# Sensor_board.net
KiCad netlist of a schematic drawn in EAGLE
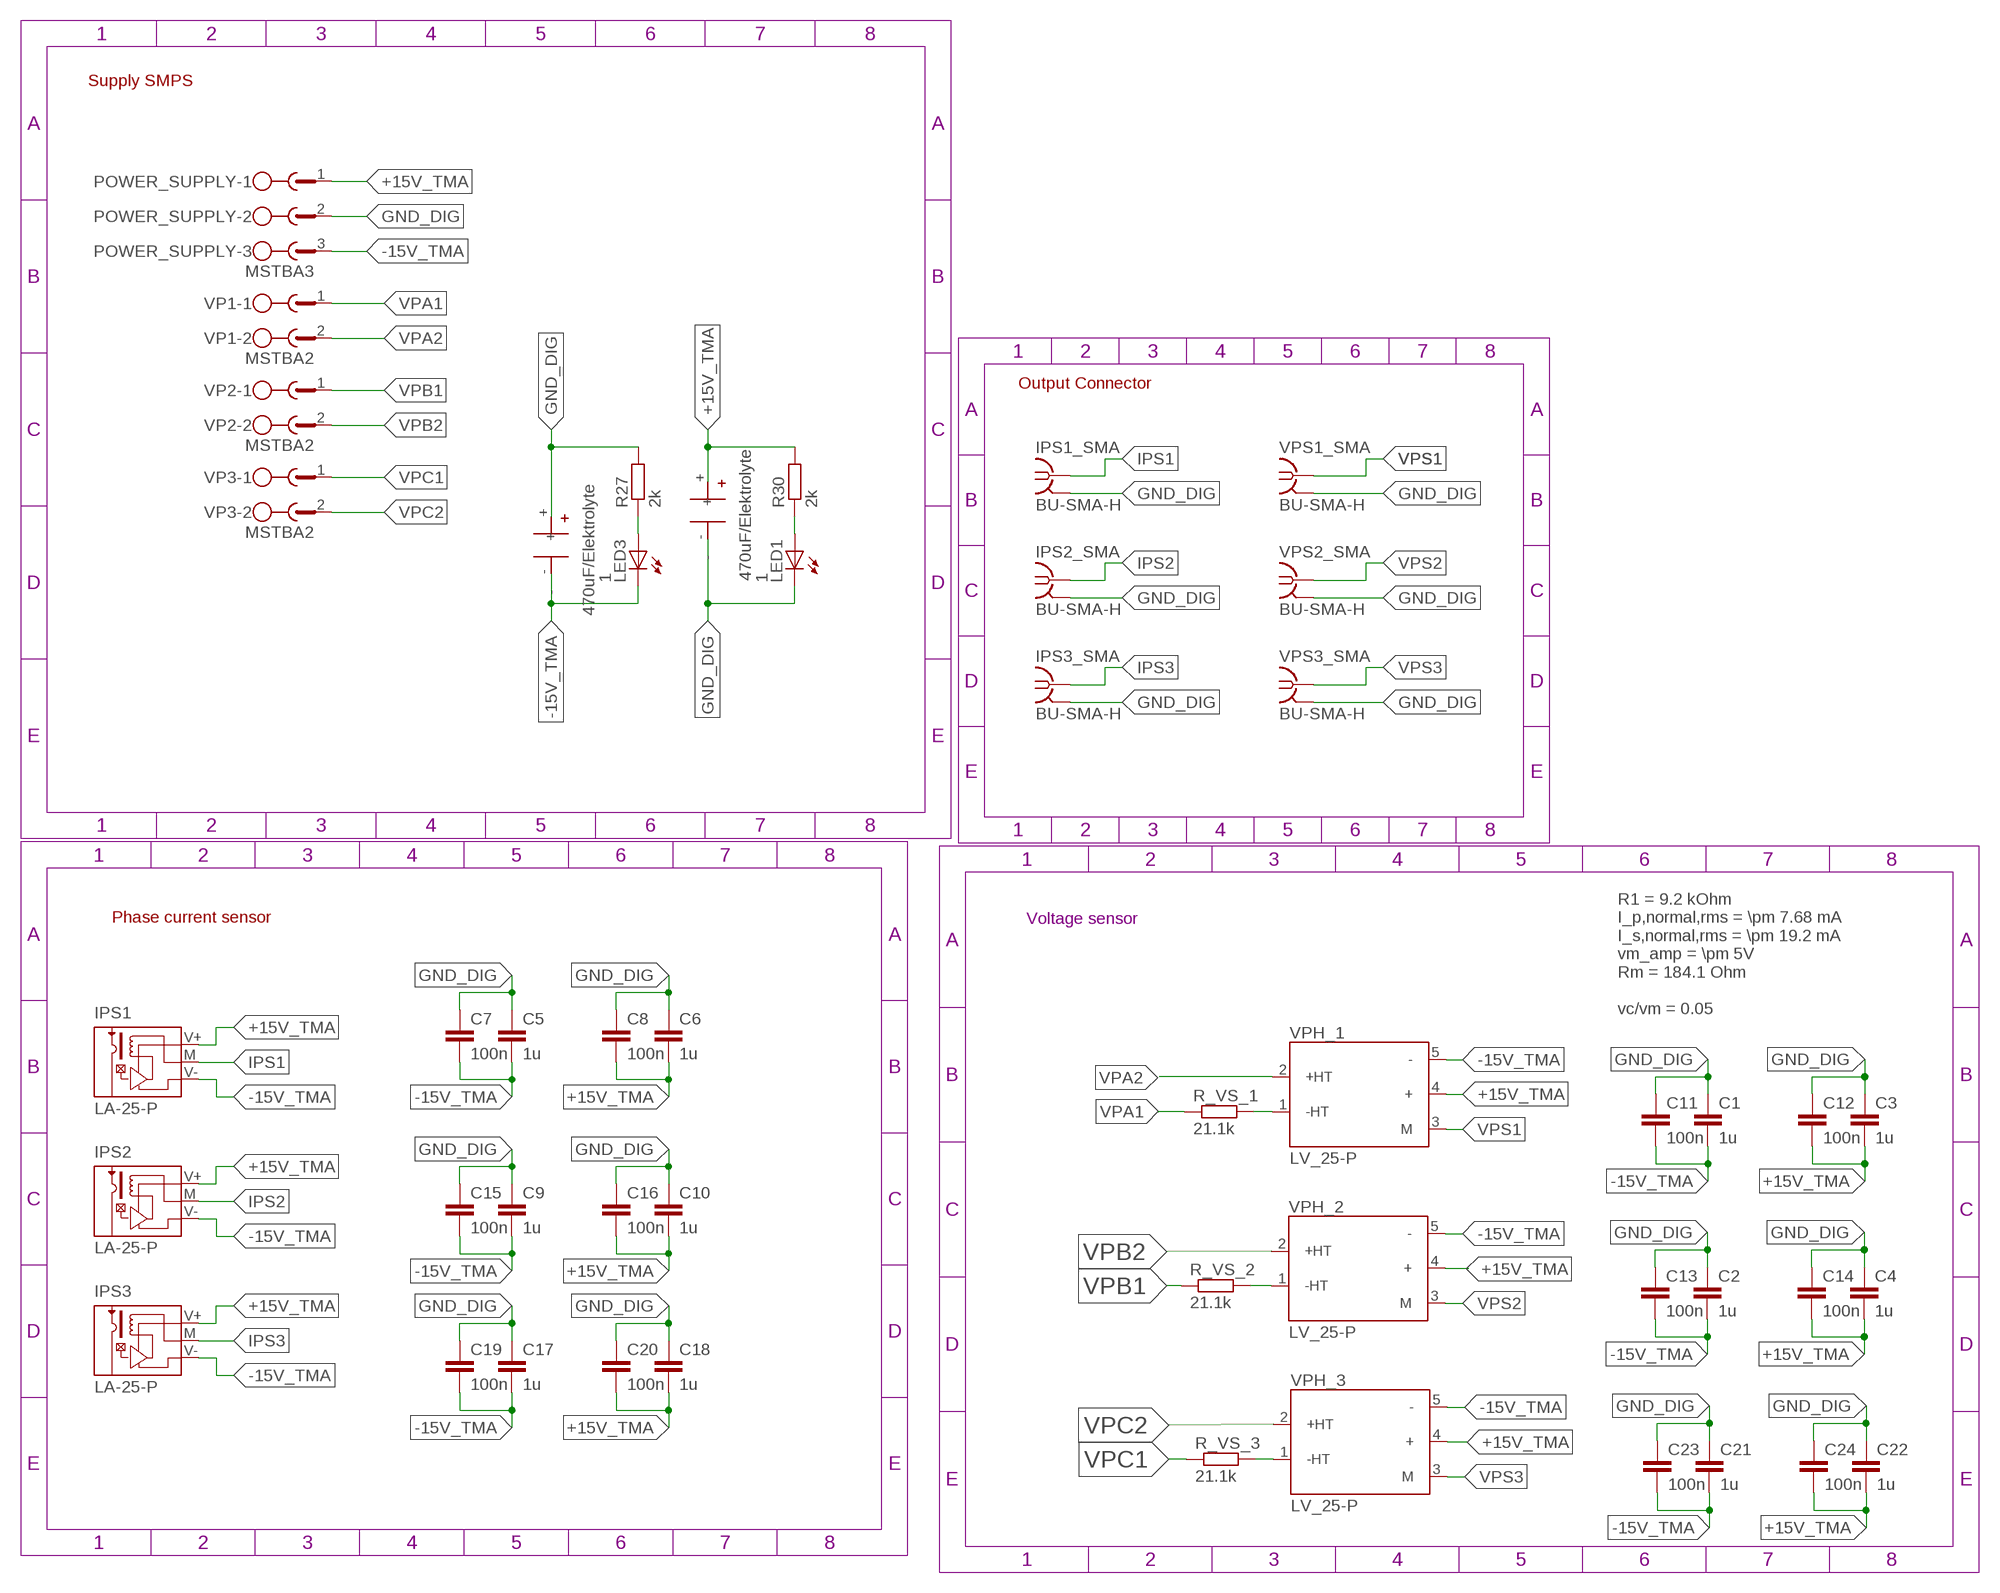
[diagram p0: schematic, sheet 1]

(export (version "E")
  (design (tool "Eeschema 10.0.6"))
  (components
    (comp (ref "C1")
      (value "1u")
      (footprint "eagle-import:C0805")
      (libsource (lib "eagle-import") (part "C-EUC0805"))
    )
    (comp (ref "C2")
      (value "1u")
      (footprint "eagle-import:C0805")
      (libsource (lib "eagle-import") (part "C-EUC0805"))
    )
    (comp (ref "C3")
      (value "1u")
      (footprint "eagle-import:C0805")
      (libsource (lib "eagle-import") (part "C-EUC0805"))
    )
    (comp (ref "C4")
      (value "1u")
      (footprint "eagle-import:C0805")
      (libsource (lib "eagle-import") (part "C-EUC0805"))
    )
    (comp (ref "C5")
      (value "1u")
      (footprint "eagle-import:C0805")
      (libsource (lib "eagle-import") (part "C-EUC0805"))
    )
    (comp (ref "C6")
      (value "1u")
      (footprint "eagle-import:C0805")
      (libsource (lib "eagle-import") (part "C-EUC0805"))
    )
    (comp (ref "C7")
      (value "100n")
      (footprint "eagle-import:C0805")
      (libsource (lib "eagle-import") (part "C-EUC0805"))
    )
    (comp (ref "C8")
      (value "100n")
      (footprint "eagle-import:C0805")
      (libsource (lib "eagle-import") (part "C-EUC0805"))
    )
    (comp (ref "C9")
      (value "1u")
      (footprint "eagle-import:C0805")
      (libsource (lib "eagle-import") (part "C-EUC0805"))
    )
    (comp (ref "C10")
      (value "1u")
      (footprint "eagle-import:C0805")
      (libsource (lib "eagle-import") (part "C-EUC0805"))
    )
    (comp (ref "C11")
      (value "100n")
      (footprint "eagle-import:C0805")
      (libsource (lib "eagle-import") (part "C-EUC0805"))
    )
    (comp (ref "C12")
      (value "100n")
      (footprint "eagle-import:C0805")
      (libsource (lib "eagle-import") (part "C-EUC0805"))
    )
    (comp (ref "C13")
      (value "100n")
      (footprint "eagle-import:C0805")
      (libsource (lib "eagle-import") (part "C-EUC0805"))
    )
    (comp (ref "C14")
      (value "100n")
      (footprint "eagle-import:C0805")
      (libsource (lib "eagle-import") (part "C-EUC0805"))
    )
    (comp (ref "C15")
      (value "100n")
      (footprint "eagle-import:C0805")
      (libsource (lib "eagle-import") (part "C-EUC0805"))
    )
    (comp (ref "C16")
      (value "100n")
      (footprint "eagle-import:C0805")
      (libsource (lib "eagle-import") (part "C-EUC0805"))
    )
    (comp (ref "C17")
      (value "1u")
      (footprint "eagle-import:C0805")
      (libsource (lib "eagle-import") (part "C-EUC0805"))
    )
    (comp (ref "C18")
      (value "1u")
      (footprint "eagle-import:C0805")
      (libsource (lib "eagle-import") (part "C-EUC0805"))
    )
    (comp (ref "C19")
      (value "100n")
      (footprint "eagle-import:C0805")
      (libsource (lib "eagle-import") (part "C-EUC0805"))
    )
    (comp (ref "C20")
      (value "100n")
      (footprint "eagle-import:C0805")
      (libsource (lib "eagle-import") (part "C-EUC0805"))
    )
    (comp (ref "C21")
      (value "1u")
      (footprint "eagle-import:C0805")
      (libsource (lib "eagle-import") (part "C-EUC0805"))
    )
    (comp (ref "C22")
      (value "1u")
      (footprint "eagle-import:C0805")
      (libsource (lib "eagle-import") (part "C-EUC0805"))
    )
    (comp (ref "C23")
      (value "100n")
      (footprint "eagle-import:C0805")
      (libsource (lib "eagle-import") (part "C-EUC0805"))
    )
    (comp (ref "C24")
      (value "100n")
      (footprint "eagle-import:C0805")
      (libsource (lib "eagle-import") (part "C-EUC0805"))
    )
    (comp (ref "C31")
      (value "ELE_C_470UF_PAN")
      (footprint "eagle-import:ELEK_C_470UF_PAN")
      (libsource (lib "eagle-import") (part "ELE_C_470UF_PAN"))
    )
    (comp (ref "C32")
      (value "ELE_C_470UF_PAN")
      (footprint "eagle-import:ELEK_C_470UF_PAN")
      (libsource (lib "eagle-import") (part "ELE_C_470UF_PAN"))
    )
    (comp (ref "IPS1")
      (value "LA-25-P")
      (footprint "eagle-import:LA25P")
      (libsource (lib "eagle-import") (part "LA-25-P"))
    )
    (comp (ref "IPS1_SMA")
      (value "BU-SMA-H")
      (footprint "eagle-import:BU-SMA-H")
      (libsource (lib "eagle-import") (part "BU-SMA-H"))
    )
    (comp (ref "IPS2")
      (value "LA-25-P")
      (footprint "eagle-import:LA25P")
      (libsource (lib "eagle-import") (part "LA-25-P"))
    )
    (comp (ref "IPS2_SMA")
      (value "BU-SMA-H")
      (footprint "eagle-import:BU-SMA-H")
      (libsource (lib "eagle-import") (part "BU-SMA-H"))
    )
    (comp (ref "IPS3")
      (value "LA-25-P")
      (footprint "eagle-import:LA25P")
      (libsource (lib "eagle-import") (part "LA-25-P"))
    )
    (comp (ref "IPS3_SMA")
      (value "BU-SMA-H")
      (footprint "eagle-import:BU-SMA-H")
      (libsource (lib "eagle-import") (part "BU-SMA-H"))
    )
    (comp (ref "LED1")
      (value "1")
      (footprint "eagle-import:CHIPLED_0805")
      (libsource (lib "eagle-import") (part "LEDCHIPLED_0805"))
    )
    (comp (ref "LED3")
      (value "1")
      (footprint "eagle-import:CHIPLED_0805")
      (libsource (lib "eagle-import") (part "LEDCHIPLED_0805"))
    )
    (comp (ref "POWER_SUPPLY")
      (value "MSTBA3")
      (footprint "eagle-import:MSTBA3")
      (fields (field (name "MF") "FARNELL") (field (name "MPN") "1757255"))
      (libsource (lib "eagle-import") (part "MSTBA3"))
    )
    (comp (ref "R27")
      (value "2k")
      (footprint "eagle-import:R0805")
      (libsource (lib "eagle-import") (part "R-EU_R0805"))
    )
    (comp (ref "R30")
      (value "2k")
      (footprint "eagle-import:R0805")
      (libsource (lib "eagle-import") (part "R-EU_R0805"))
    )
    (comp (ref "R_VS_1")
      (value "21.1k")
      (footprint "eagle-import:0414_15")
      (libsource (lib "eagle-import") (part "R-EU_0414/15"))
    )
    (comp (ref "R_VS_2")
      (value "21.1k")
      (footprint "eagle-import:0414_15")
      (libsource (lib "eagle-import") (part "R-EU_0414/15"))
    )
    (comp (ref "R_VS_3")
      (value "21.1k")
      (footprint "eagle-import:0414_15")
      (libsource (lib "eagle-import") (part "R-EU_0414/15"))
    )
    (comp (ref "VP1")
      (value "MSTBA2")
      (footprint "eagle-import:MSTBA2")
      (fields (field (name "MF") "FARNELL") (field (name "MPN") "1757242"))
      (libsource (lib "eagle-import") (part "MSTBA2"))
    )
    (comp (ref "VP2")
      (value "MSTBA2")
      (footprint "eagle-import:MSTBA2")
      (fields (field (name "MF") "FARNELL") (field (name "MPN") "1757242"))
      (libsource (lib "eagle-import") (part "MSTBA2"))
    )
    (comp (ref "VP3")
      (value "MSTBA2")
      (footprint "eagle-import:MSTBA2")
      (fields (field (name "MF") "FARNELL") (field (name "MPN") "1757242"))
      (libsource (lib "eagle-import") (part "MSTBA2"))
    )
    (comp (ref "VPH_1")
      (value "LV_25-P")
      (footprint "eagle-import:XDCR_LV25-P")
      (fields
        (field (name "DIGI-KEY_PART_NUMBER") "398-1019-ND")
        (field (name "MF") "LEM USA")
        (field (name "MP") "LV 25-P")
      )
      (libsource (lib "eagle-import") (part "LV_25-P"))
    )
    (comp (ref "VPH_2")
      (value "LV_25-P")
      (footprint "eagle-import:XDCR_LV25-P")
      (fields
        (field (name "DIGI-KEY_PART_NUMBER") "398-1019-ND")
        (field (name "MF") "LEM USA")
        (field (name "MP") "LV 25-P")
      )
      (libsource (lib "eagle-import") (part "LV_25-P"))
    )
    (comp (ref "VPH_3")
      (value "LV_25-P")
      (footprint "eagle-import:XDCR_LV25-P")
      (fields
        (field (name "DIGI-KEY_PART_NUMBER") "398-1019-ND")
        (field (name "MF") "LEM USA")
        (field (name "MP") "LV 25-P")
      )
      (libsource (lib "eagle-import") (part "LV_25-P"))
    )
    (comp (ref "VPS1_SMA")
      (value "BU-SMA-H")
      (footprint "eagle-import:BU-SMA-H")
      (libsource (lib "eagle-import") (part "BU-SMA-H"))
    )
    (comp (ref "VPS2_SMA")
      (value "BU-SMA-H")
      (footprint "eagle-import:BU-SMA-H")
      (libsource (lib "eagle-import") (part "BU-SMA-H"))
    )
    (comp (ref "VPS3_SMA")
      (value "BU-SMA-H")
      (footprint "eagle-import:BU-SMA-H")
      (libsource (lib "eagle-import") (part "BU-SMA-H"))
    )
  )
  (nets
    (net (code "1") (name "+15V_TMA") (class "Default")
      (node (ref "C10") (pin "2") (pinfunction "2_2") (pintype "passive"))
      (node (ref "C12") (pin "2") (pinfunction "2_2") (pintype "passive"))
      (node (ref "C14") (pin "2") (pinfunction "2_2") (pintype "passive"))
      (node (ref "C16") (pin "2") (pinfunction "2_2") (pintype "passive"))
      (node (ref "C18") (pin "2") (pinfunction "2_2") (pintype "passive"))
      (node (ref "C20") (pin "2") (pinfunction "2_2") (pintype "passive"))
      (node (ref "C22") (pin "2") (pinfunction "2_2") (pintype "passive"))
      (node (ref "C24") (pin "2") (pinfunction "2_2") (pintype "passive"))
      (node (ref "C3") (pin "2") (pinfunction "2_2") (pintype "passive"))
      (node (ref "C32") (pin "+") (pinfunction "+_+") (pintype "bidirectional"))
      (node (ref "C4") (pin "2") (pinfunction "2_2") (pintype "passive"))
      (node (ref "C6") (pin "2") (pinfunction "2_2") (pintype "passive"))
      (node (ref "C8") (pin "2") (pinfunction "2_2") (pintype "passive"))
      (node (ref "IPS1") (pin "V+") (pinfunction "V+_V+") (pintype "input"))
      (node (ref "IPS2") (pin "V+") (pinfunction "V+_V+") (pintype "input"))
      (node (ref "IPS3") (pin "V+") (pinfunction "V+_V+") (pintype "input"))
      (node (ref "POWER_SUPPLY") (pin "1") (pinfunction "1_1") (pintype "passive"))
      (node (ref "R30") (pin "2") (pinfunction "2_2") (pintype "passive"))
      (node (ref "VPH_1") (pin "4") (pinfunction "+_4") (pintype "output"))
      (node (ref "VPH_2") (pin "4") (pinfunction "+_4") (pintype "output"))
      (node (ref "VPH_3") (pin "4") (pinfunction "+_4") (pintype "output"))
    )
    (net (code "2") (name "-15V_TMA") (class "Default")
      (node (ref "C1") (pin "2") (pinfunction "2_2") (pintype "passive"))
      (node (ref "C11") (pin "2") (pinfunction "2_2") (pintype "passive"))
      (node (ref "C13") (pin "2") (pinfunction "2_2") (pintype "passive"))
      (node (ref "C15") (pin "2") (pinfunction "2_2") (pintype "passive"))
      (node (ref "C17") (pin "2") (pinfunction "2_2") (pintype "passive"))
      (node (ref "C19") (pin "2") (pinfunction "2_2") (pintype "passive"))
      (node (ref "C2") (pin "2") (pinfunction "2_2") (pintype "passive"))
      (node (ref "C21") (pin "2") (pinfunction "2_2") (pintype "passive"))
      (node (ref "C23") (pin "2") (pinfunction "2_2") (pintype "passive"))
      (node (ref "C31") (pin "-") (pinfunction "-_-") (pintype "bidirectional"))
      (node (ref "C5") (pin "2") (pinfunction "2_2") (pintype "passive"))
      (node (ref "C7") (pin "2") (pinfunction "2_2") (pintype "passive"))
      (node (ref "C9") (pin "2") (pinfunction "2_2") (pintype "passive"))
      (node (ref "IPS1") (pin "V-") (pinfunction "V-_V-") (pintype "input"))
      (node (ref "IPS2") (pin "V-") (pinfunction "V-_V-") (pintype "input"))
      (node (ref "IPS3") (pin "V-") (pinfunction "V-_V-") (pintype "input"))
      (node (ref "LED3") (pin "C") (pinfunction "C_C") (pintype "passive"))
      (node (ref "POWER_SUPPLY") (pin "3") (pinfunction "1_3") (pintype "passive"))
      (node (ref "VPH_1") (pin "5") (pinfunction "-_5") (pintype "output"))
      (node (ref "VPH_2") (pin "5") (pinfunction "-_5") (pintype "output"))
      (node (ref "VPH_3") (pin "5") (pinfunction "-_5") (pintype "output"))
    )
    (net (code "3") (name "GND_DIG") (class "Default")
      (node (ref "C1") (pin "1") (pinfunction "1_1") (pintype "passive"))
      (node (ref "C10") (pin "1") (pinfunction "1_1") (pintype "passive"))
      (node (ref "C11") (pin "1") (pinfunction "1_1") (pintype "passive"))
      (node (ref "C12") (pin "1") (pinfunction "1_1") (pintype "passive"))
      (node (ref "C13") (pin "1") (pinfunction "1_1") (pintype "passive"))
      (node (ref "C14") (pin "1") (pinfunction "1_1") (pintype "passive"))
      (node (ref "C15") (pin "1") (pinfunction "1_1") (pintype "passive"))
      (node (ref "C16") (pin "1") (pinfunction "1_1") (pintype "passive"))
      (node (ref "C17") (pin "1") (pinfunction "1_1") (pintype "passive"))
      (node (ref "C18") (pin "1") (pinfunction "1_1") (pintype "passive"))
      (node (ref "C19") (pin "1") (pinfunction "1_1") (pintype "passive"))
      (node (ref "C2") (pin "1") (pinfunction "1_1") (pintype "passive"))
      (node (ref "C20") (pin "1") (pinfunction "1_1") (pintype "passive"))
      (node (ref "C21") (pin "1") (pinfunction "1_1") (pintype "passive"))
      (node (ref "C22") (pin "1") (pinfunction "1_1") (pintype "passive"))
      (node (ref "C23") (pin "1") (pinfunction "1_1") (pintype "passive"))
      (node (ref "C24") (pin "1") (pinfunction "1_1") (pintype "passive"))
      (node (ref "C3") (pin "1") (pinfunction "1_1") (pintype "passive"))
      (node (ref "C31") (pin "+") (pinfunction "+_+") (pintype "bidirectional"))
      (node (ref "C32") (pin "-") (pinfunction "-_-") (pintype "bidirectional"))
      (node (ref "C4") (pin "1") (pinfunction "1_1") (pintype "passive"))
      (node (ref "C5") (pin "1") (pinfunction "1_1") (pintype "passive"))
      (node (ref "C6") (pin "1") (pinfunction "1_1") (pintype "passive"))
      (node (ref "C7") (pin "1") (pinfunction "1_1") (pintype "passive"))
      (node (ref "C8") (pin "1") (pinfunction "1_1") (pintype "passive"))
      (node (ref "C9") (pin "1") (pinfunction "1_1") (pintype "passive"))
      (node (ref "IPS1_SMA") (pin "2") (pinfunction "2_2") (pintype "passive"))
      (node (ref "IPS1_SMA") (pin "3") (pinfunction "2_3") (pintype "passive"))
      (node (ref "IPS1_SMA") (pin "4") (pinfunction "2_4") (pintype "passive"))
      (node (ref "IPS1_SMA") (pin "5") (pinfunction "2_5") (pintype "passive"))
      (node (ref "IPS2_SMA") (pin "2") (pinfunction "2_2") (pintype "passive"))
      (node (ref "IPS2_SMA") (pin "3") (pinfunction "2_3") (pintype "passive"))
      (node (ref "IPS2_SMA") (pin "4") (pinfunction "2_4") (pintype "passive"))
      (node (ref "IPS2_SMA") (pin "5") (pinfunction "2_5") (pintype "passive"))
      (node (ref "IPS3_SMA") (pin "2") (pinfunction "2_2") (pintype "passive"))
      (node (ref "IPS3_SMA") (pin "3") (pinfunction "2_3") (pintype "passive"))
      (node (ref "IPS3_SMA") (pin "4") (pinfunction "2_4") (pintype "passive"))
      (node (ref "IPS3_SMA") (pin "5") (pinfunction "2_5") (pintype "passive"))
      (node (ref "LED1") (pin "C") (pinfunction "C_C") (pintype "passive"))
      (node (ref "POWER_SUPPLY") (pin "2") (pinfunction "1_2") (pintype "passive"))
      (node (ref "R27") (pin "2") (pinfunction "2_2") (pintype "passive"))
      (node (ref "VPS1_SMA") (pin "2") (pinfunction "2_2") (pintype "passive"))
      (node (ref "VPS1_SMA") (pin "3") (pinfunction "2_3") (pintype "passive"))
      (node (ref "VPS1_SMA") (pin "4") (pinfunction "2_4") (pintype "passive"))
      (node (ref "VPS1_SMA") (pin "5") (pinfunction "2_5") (pintype "passive"))
      (node (ref "VPS2_SMA") (pin "2") (pinfunction "2_2") (pintype "passive"))
      (node (ref "VPS2_SMA") (pin "3") (pinfunction "2_3") (pintype "passive"))
      (node (ref "VPS2_SMA") (pin "4") (pinfunction "2_4") (pintype "passive"))
      (node (ref "VPS2_SMA") (pin "5") (pinfunction "2_5") (pintype "passive"))
      (node (ref "VPS3_SMA") (pin "2") (pinfunction "2_2") (pintype "passive"))
      (node (ref "VPS3_SMA") (pin "3") (pinfunction "2_3") (pintype "passive"))
      (node (ref "VPS3_SMA") (pin "4") (pinfunction "2_4") (pintype "passive"))
      (node (ref "VPS3_SMA") (pin "5") (pinfunction "2_5") (pintype "passive"))
    )
    (net (code "4") (name "IPS1") (class "Default")
      (node (ref "IPS1") (pin "M") (pinfunction "M_M") (pintype "output"))
      (node (ref "IPS1_SMA") (pin "1") (pinfunction "1_1") (pintype "passive"))
    )
    (net (code "5") (name "IPS2") (class "Default")
      (node (ref "IPS2") (pin "M") (pinfunction "M_M") (pintype "output"))
      (node (ref "IPS2_SMA") (pin "1") (pinfunction "1_1") (pintype "passive"))
    )
    (net (code "6") (name "IPS3") (class "Default")
      (node (ref "IPS3") (pin "M") (pinfunction "M_M") (pintype "output"))
      (node (ref "IPS3_SMA") (pin "1") (pinfunction "1_1") (pintype "passive"))
    )
    (net (code "7") (name "Net-(LED1-PadA)") (class "Default")
      (node (ref "LED1") (pin "A") (pinfunction "A_A") (pintype "passive"))
      (node (ref "R30") (pin "1") (pinfunction "1_1") (pintype "passive"))
    )
    (net (code "8") (name "Net-(LED3-PadA)") (class "Default")
      (node (ref "LED3") (pin "A") (pinfunction "A_A") (pintype "passive"))
      (node (ref "R27") (pin "1") (pinfunction "1_1") (pintype "passive"))
    )
    (net (code "9") (name "Net-(VPH_1--HT)") (class "Default")
      (node (ref "R_VS_1") (pin "2") (pinfunction "2_2") (pintype "passive"))
      (node (ref "VPH_1") (pin "1") (pinfunction "-HT_1") (pintype "input"))
    )
    (net (code "10") (name "Net-(VPH_2--HT)") (class "Default")
      (node (ref "R_VS_2") (pin "2") (pinfunction "2_2") (pintype "passive"))
      (node (ref "VPH_2") (pin "1") (pinfunction "-HT_1") (pintype "input"))
    )
    (net (code "11") (name "Net-(VPH_3--HT)") (class "Default")
      (node (ref "R_VS_3") (pin "2") (pinfunction "2_2") (pintype "passive"))
      (node (ref "VPH_3") (pin "1") (pinfunction "-HT_1") (pintype "input"))
    )
    (net (code "12") (name "VPA1") (class "Default")
      (node (ref "R_VS_1") (pin "1") (pinfunction "1_1") (pintype "passive"))
      (node (ref "VP1") (pin "1") (pinfunction "1_1") (pintype "passive"))
    )
    (net (code "13") (name "VPA2") (class "Default")
      (node (ref "VP1") (pin "2") (pinfunction "1_2") (pintype "passive"))
      (node (ref "VPH_1") (pin "2") (pinfunction "+HT_2") (pintype "input"))
    )
    (net (code "14") (name "VPB1") (class "Default")
      (node (ref "R_VS_2") (pin "1") (pinfunction "1_1") (pintype "passive"))
      (node (ref "VP2") (pin "1") (pinfunction "1_1") (pintype "passive"))
    )
    (net (code "15") (name "VPB2") (class "Default")
      (node (ref "VP2") (pin "2") (pinfunction "1_2") (pintype "passive"))
      (node (ref "VPH_2") (pin "2") (pinfunction "+HT_2") (pintype "input"))
    )
    (net (code "16") (name "VPC1") (class "Default")
      (node (ref "R_VS_3") (pin "1") (pinfunction "1_1") (pintype "passive"))
      (node (ref "VP3") (pin "1") (pinfunction "1_1") (pintype "passive"))
    )
    (net (code "17") (name "VPC2") (class "Default")
      (node (ref "VP3") (pin "2") (pinfunction "1_2") (pintype "passive"))
      (node (ref "VPH_3") (pin "2") (pinfunction "+HT_2") (pintype "input"))
    )
    (net (code "18") (name "VPS1") (class "Default")
      (node (ref "VPH_1") (pin "3") (pinfunction "M_3") (pintype "output"))
      (node (ref "VPS1_SMA") (pin "1") (pinfunction "1_1") (pintype "passive"))
    )
    (net (code "19") (name "VPS2") (class "Default")
      (node (ref "VPH_2") (pin "3") (pinfunction "M_3") (pintype "output"))
      (node (ref "VPS2_SMA") (pin "1") (pinfunction "1_1") (pintype "passive"))
    )
    (net (code "20") (name "VPS3") (class "Default")
      (node (ref "VPH_3") (pin "3") (pinfunction "M_3") (pintype "output"))
      (node (ref "VPS3_SMA") (pin "1") (pinfunction "1_1") (pintype "passive"))
    )
  )
)
